# BottomSide.net
KiCad netlist of a schematic drawn in Altium Designer
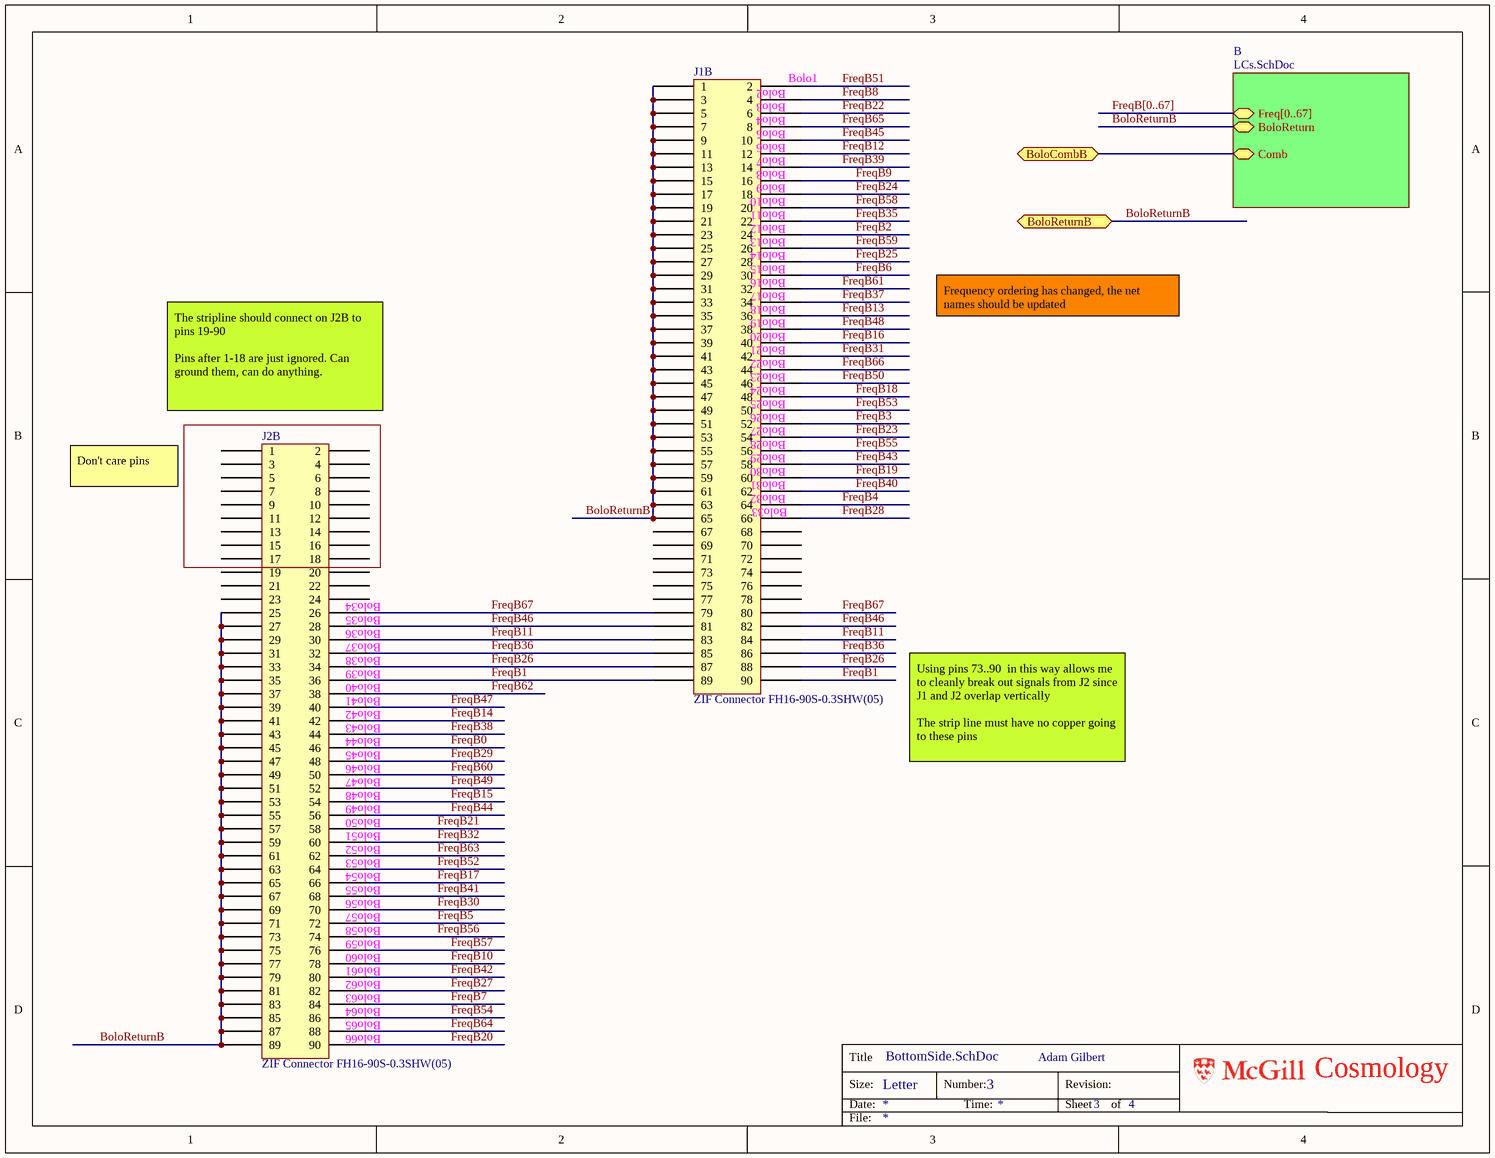
[diagram p0: BottomSide.SchDoc]

(export (version "E")
  (design (tool "Eeschema 10.0.6"))
  (components
    (comp (ref "J1B")
      (value "ZIF Connector FH16-90S-0.3SHW(05)")
      (footprint "LCBoard_ZIFCon")
      (libsource (lib "SPT3G_LCBoard") (part "LCboard_FH16-90S-0.3SHW(05)"))
    )
    (comp (ref "J2B")
      (value "ZIF Connector FH16-90S-0.3SHW(05)")
      (footprint "LCBoard_ZIFCon")
      (libsource (lib "SPT3G_LCBoard") (part "LCboard_FH16-90S-0.3SHW(05)"))
    )
  )
  (nets
    (net (code "4") (name "/BoloReturnB") (class "Default")
      (node (ref "J1B") (pin "1") (pinfunction "1_1") (pintype "passive"))
      (node (ref "J1B") (pin "11") (pinfunction "11_11") (pintype "passive"))
      (node (ref "J1B") (pin "13") (pinfunction "13_13") (pintype "passive"))
      (node (ref "J1B") (pin "15") (pinfunction "15_15") (pintype "passive"))
      (node (ref "J1B") (pin "17") (pinfunction "17_17") (pintype "passive"))
      (node (ref "J1B") (pin "19") (pinfunction "19_19") (pintype "passive"))
      (node (ref "J1B") (pin "21") (pinfunction "21_21") (pintype "passive"))
      (node (ref "J1B") (pin "23") (pinfunction "23_23") (pintype "passive"))
      (node (ref "J1B") (pin "25") (pinfunction "25_25") (pintype "passive"))
      (node (ref "J1B") (pin "27") (pinfunction "27_27") (pintype "passive"))
      (node (ref "J1B") (pin "29") (pinfunction "29_29") (pintype "passive"))
      (node (ref "J1B") (pin "3") (pinfunction "3_3") (pintype "passive"))
      (node (ref "J1B") (pin "31") (pinfunction "31_31") (pintype "passive"))
      (node (ref "J1B") (pin "33") (pinfunction "33_33") (pintype "passive"))
      (node (ref "J1B") (pin "35") (pinfunction "35_35") (pintype "passive"))
      (node (ref "J1B") (pin "37") (pinfunction "37_37") (pintype "passive"))
      (node (ref "J1B") (pin "39") (pinfunction "39_39") (pintype "passive"))
      (node (ref "J1B") (pin "41") (pinfunction "41_41") (pintype "passive"))
      (node (ref "J1B") (pin "43") (pinfunction "43_43") (pintype "passive"))
      (node (ref "J1B") (pin "45") (pinfunction "45_45") (pintype "passive"))
      (node (ref "J1B") (pin "47") (pinfunction "47_47") (pintype "passive"))
      (node (ref "J1B") (pin "49") (pinfunction "49_49") (pintype "passive"))
      (node (ref "J1B") (pin "5") (pinfunction "5_5") (pintype "passive"))
      (node (ref "J1B") (pin "51") (pinfunction "51_51") (pintype "passive"))
      (node (ref "J1B") (pin "53") (pinfunction "53_53") (pintype "passive"))
      (node (ref "J1B") (pin "55") (pinfunction "55_55") (pintype "passive"))
      (node (ref "J1B") (pin "57") (pinfunction "57_57") (pintype "passive"))
      (node (ref "J1B") (pin "59") (pinfunction "59_59") (pintype "passive"))
      (node (ref "J1B") (pin "61") (pinfunction "61_61") (pintype "passive"))
      (node (ref "J1B") (pin "63") (pinfunction "63_63") (pintype "passive"))
      (node (ref "J1B") (pin "65") (pinfunction "65_65") (pintype "passive"))
      (node (ref "J1B") (pin "7") (pinfunction "7_7") (pintype "passive"))
      (node (ref "J1B") (pin "9") (pinfunction "9_9") (pintype "passive"))
      (node (ref "J2B") (pin "25") (pinfunction "25_25") (pintype "passive"))
      (node (ref "J2B") (pin "27") (pinfunction "27_27") (pintype "passive"))
      (node (ref "J2B") (pin "29") (pinfunction "29_29") (pintype "passive"))
      (node (ref "J2B") (pin "31") (pinfunction "31_31") (pintype "passive"))
      (node (ref "J2B") (pin "33") (pinfunction "33_33") (pintype "passive"))
      (node (ref "J2B") (pin "35") (pinfunction "35_35") (pintype "passive"))
      (node (ref "J2B") (pin "37") (pinfunction "37_37") (pintype "passive"))
      (node (ref "J2B") (pin "39") (pinfunction "39_39") (pintype "passive"))
      (node (ref "J2B") (pin "41") (pinfunction "41_41") (pintype "passive"))
      (node (ref "J2B") (pin "43") (pinfunction "43_43") (pintype "passive"))
      (node (ref "J2B") (pin "45") (pinfunction "45_45") (pintype "passive"))
      (node (ref "J2B") (pin "47") (pinfunction "47_47") (pintype "passive"))
      (node (ref "J2B") (pin "49") (pinfunction "49_49") (pintype "passive"))
      (node (ref "J2B") (pin "51") (pinfunction "51_51") (pintype "passive"))
      (node (ref "J2B") (pin "53") (pinfunction "53_53") (pintype "passive"))
      (node (ref "J2B") (pin "55") (pinfunction "55_55") (pintype "passive"))
      (node (ref "J2B") (pin "57") (pinfunction "57_57") (pintype "passive"))
      (node (ref "J2B") (pin "59") (pinfunction "59_59") (pintype "passive"))
      (node (ref "J2B") (pin "61") (pinfunction "61_61") (pintype "passive"))
      (node (ref "J2B") (pin "63") (pinfunction "63_63") (pintype "passive"))
      (node (ref "J2B") (pin "65") (pinfunction "65_65") (pintype "passive"))
      (node (ref "J2B") (pin "67") (pinfunction "67_67") (pintype "passive"))
      (node (ref "J2B") (pin "69") (pinfunction "69_69") (pintype "passive"))
      (node (ref "J2B") (pin "71") (pinfunction "71_71") (pintype "passive"))
      (node (ref "J2B") (pin "73") (pinfunction "73_73") (pintype "passive"))
      (node (ref "J2B") (pin "75") (pinfunction "75_75") (pintype "passive"))
      (node (ref "J2B") (pin "77") (pinfunction "77_77") (pintype "passive"))
      (node (ref "J2B") (pin "79") (pinfunction "79_79") (pintype "passive"))
      (node (ref "J2B") (pin "81") (pinfunction "81_81") (pintype "passive"))
      (node (ref "J2B") (pin "83") (pinfunction "83_83") (pintype "passive"))
      (node (ref "J2B") (pin "85") (pinfunction "85_85") (pintype "passive"))
      (node (ref "J2B") (pin "87") (pinfunction "87_87") (pintype "passive"))
      (node (ref "J2B") (pin "89") (pinfunction "89_89") (pintype "passive"))
    )
    (net (code "5") (name "/FreqB0") (class "Default")
      (node (ref "J2B") (pin "46") (pinfunction "46_46") (pintype "passive"))
    )
    (net (code "6") (name "/FreqB1") (class "Default")
      (node (ref "J1B") (pin "89") (pinfunction "89_89") (pintype "passive"))
      (node (ref "J1B") (pin "90") (pinfunction "90_90") (pintype "passive"))
      (node (ref "J2B") (pin "36") (pinfunction "36_36") (pintype "passive"))
    )
    (net (code "7") (name "/FreqB2") (class "Default")
      (node (ref "J1B") (pin "24") (pinfunction "24_24") (pintype "passive"))
    )
    (net (code "8") (name "/FreqB3") (class "Default")
      (node (ref "J1B") (pin "52") (pinfunction "52_52") (pintype "passive"))
    )
    (net (code "9") (name "/FreqB4") (class "Default")
      (node (ref "J1B") (pin "64") (pinfunction "64_64") (pintype "passive"))
    )
    (net (code "10") (name "/FreqB5") (class "Default")
      (node (ref "J2B") (pin "72") (pinfunction "72_72") (pintype "passive"))
    )
    (net (code "11") (name "/FreqB6") (class "Default")
      (node (ref "J1B") (pin "30") (pinfunction "30_30") (pintype "passive"))
    )
    (net (code "12") (name "/FreqB7") (class "Default")
      (node (ref "J2B") (pin "84") (pinfunction "84_84") (pintype "passive"))
    )
    (net (code "13") (name "/FreqB8") (class "Default")
      (node (ref "J1B") (pin "4") (pinfunction "4_4") (pintype "passive"))
    )
    (net (code "14") (name "/FreqB9") (class "Default")
      (node (ref "J1B") (pin "16") (pinfunction "16_16") (pintype "passive"))
    )
    (net (code "15") (name "/FreqB10") (class "Default")
      (node (ref "J2B") (pin "78") (pinfunction "78_78") (pintype "passive"))
    )
    (net (code "16") (name "/FreqB11") (class "Default")
      (node (ref "J1B") (pin "83") (pinfunction "83_83") (pintype "passive"))
      (node (ref "J1B") (pin "84") (pinfunction "84_84") (pintype "passive"))
      (node (ref "J2B") (pin "30") (pinfunction "30_30") (pintype "passive"))
    )
    (net (code "17") (name "/FreqB12") (class "Default")
      (node (ref "J1B") (pin "12") (pinfunction "12_12") (pintype "passive"))
    )
    (net (code "18") (name "/FreqB13") (class "Default")
      (node (ref "J1B") (pin "36") (pinfunction "36_36") (pintype "passive"))
    )
    (net (code "19") (name "/FreqB14") (class "Default")
      (node (ref "J2B") (pin "42") (pinfunction "42_42") (pintype "passive"))
    )
    (net (code "20") (name "/FreqB15") (class "Default")
      (node (ref "J2B") (pin "54") (pinfunction "54_54") (pintype "passive"))
    )
    (net (code "21") (name "/FreqB16") (class "Default")
      (node (ref "J1B") (pin "40") (pinfunction "40_40") (pintype "passive"))
    )
    (net (code "22") (name "/FreqB17") (class "Default")
      (node (ref "J2B") (pin "66") (pinfunction "66_66") (pintype "passive"))
    )
    (net (code "23") (name "/FreqB18") (class "Default")
      (node (ref "J1B") (pin "48") (pinfunction "48_48") (pintype "passive"))
    )
    (net (code "24") (name "/FreqB19") (class "Default")
      (node (ref "J1B") (pin "60") (pinfunction "60_60") (pintype "passive"))
    )
    (net (code "25") (name "/FreqB20") (class "Default")
      (node (ref "J2B") (pin "90") (pinfunction "90_90") (pintype "passive"))
    )
    (net (code "26") (name "/FreqB21") (class "Default")
      (node (ref "J2B") (pin "58") (pinfunction "58_58") (pintype "passive"))
    )
    (net (code "27") (name "/FreqB22") (class "Default")
      (node (ref "J1B") (pin "6") (pinfunction "6_6") (pintype "passive"))
    )
    (net (code "28") (name "/FreqB23") (class "Default")
      (node (ref "J1B") (pin "54") (pinfunction "54_54") (pintype "passive"))
    )
    (net (code "29") (name "/FreqB24") (class "Default")
      (node (ref "J1B") (pin "18") (pinfunction "18_18") (pintype "passive"))
    )
    (net (code "30") (name "/FreqB25") (class "Default")
      (node (ref "J1B") (pin "28") (pinfunction "28_28") (pintype "passive"))
    )
    (net (code "31") (name "/FreqB26") (class "Default")
      (node (ref "J1B") (pin "87") (pinfunction "87_87") (pintype "passive"))
      (node (ref "J1B") (pin "88") (pinfunction "88_88") (pintype "passive"))
      (node (ref "J2B") (pin "34") (pinfunction "34_34") (pintype "passive"))
    )
    (net (code "32") (name "/FreqB27") (class "Default")
      (node (ref "J2B") (pin "82") (pinfunction "82_82") (pintype "passive"))
    )
    (net (code "33") (name "/FreqB28") (class "Default")
      (node (ref "J1B") (pin "66") (pinfunction "66_66") (pintype "passive"))
    )
    (net (code "34") (name "/FreqB29") (class "Default")
      (node (ref "J2B") (pin "48") (pinfunction "48_48") (pintype "passive"))
    )
    (net (code "35") (name "/FreqB30") (class "Default")
      (node (ref "J2B") (pin "70") (pinfunction "70_70") (pintype "passive"))
    )
    (net (code "36") (name "/FreqB31") (class "Default")
      (node (ref "J1B") (pin "42") (pinfunction "42_42") (pintype "passive"))
    )
    (net (code "37") (name "/FreqB32") (class "Default")
      (node (ref "J2B") (pin "60") (pinfunction "60_60") (pintype "passive"))
    )
    (net (code "38") (name "/FreqB35") (class "Default")
      (node (ref "J1B") (pin "22") (pinfunction "22_22") (pintype "passive"))
    )
    (net (code "39") (name "/FreqB36") (class "Default")
      (node (ref "J1B") (pin "85") (pinfunction "85_85") (pintype "passive"))
      (node (ref "J1B") (pin "86") (pinfunction "86_86") (pintype "passive"))
      (node (ref "J2B") (pin "32") (pinfunction "32_32") (pintype "passive"))
    )
    (net (code "40") (name "/FreqB37") (class "Default")
      (node (ref "J1B") (pin "34") (pinfunction "34_34") (pintype "passive"))
    )
    (net (code "41") (name "/FreqB38") (class "Default")
      (node (ref "J2B") (pin "44") (pinfunction "44_44") (pintype "passive"))
    )
    (net (code "42") (name "/FreqB39") (class "Default")
      (node (ref "J1B") (pin "14") (pinfunction "14_14") (pintype "passive"))
    )
    (net (code "43") (name "/FreqB40") (class "Default")
      (node (ref "J1B") (pin "62") (pinfunction "62_62") (pintype "passive"))
    )
    (net (code "44") (name "/FreqB41") (class "Default")
      (node (ref "J2B") (pin "68") (pinfunction "68_68") (pintype "passive"))
    )
    (net (code "45") (name "/FreqB42") (class "Default")
      (node (ref "J2B") (pin "80") (pinfunction "80_80") (pintype "passive"))
    )
    (net (code "46") (name "/FreqB43") (class "Default")
      (node (ref "J1B") (pin "58") (pinfunction "58_58") (pintype "passive"))
    )
    (net (code "47") (name "/FreqB44") (class "Default")
      (node (ref "J2B") (pin "56") (pinfunction "56_56") (pintype "passive"))
    )
    (net (code "48") (name "/FreqB45") (class "Default")
      (node (ref "J1B") (pin "10") (pinfunction "10_10") (pintype "passive"))
    )
    (net (code "49") (name "/FreqB46") (class "Default")
      (node (ref "J1B") (pin "81") (pinfunction "81_81") (pintype "passive"))
      (node (ref "J1B") (pin "82") (pinfunction "82_82") (pintype "passive"))
      (node (ref "J2B") (pin "28") (pinfunction "28_28") (pintype "passive"))
    )
    (net (code "50") (name "/FreqB47") (class "Default")
      (node (ref "J2B") (pin "40") (pinfunction "40_40") (pintype "passive"))
    )
    (net (code "51") (name "/FreqB48") (class "Default")
      (node (ref "J1B") (pin "38") (pinfunction "38_38") (pintype "passive"))
    )
    (net (code "52") (name "/FreqB49") (class "Default")
      (node (ref "J2B") (pin "52") (pinfunction "52_52") (pintype "passive"))
    )
    (net (code "53") (name "/FreqB50") (class "Default")
      (node (ref "J1B") (pin "46") (pinfunction "46_46") (pintype "passive"))
    )
    (net (code "54") (name "/FreqB51") (class "Default")
      (node (ref "J1B") (pin "2") (pinfunction "2_2") (pintype "passive"))
    )
    (net (code "55") (name "/FreqB52") (class "Default")
      (node (ref "J2B") (pin "64") (pinfunction "64_64") (pintype "passive"))
    )
    (net (code "56") (name "/FreqB53") (class "Default")
      (node (ref "J1B") (pin "50") (pinfunction "50_50") (pintype "passive"))
    )
    (net (code "57") (name "/FreqB54") (class "Default")
      (node (ref "J2B") (pin "86") (pinfunction "86_86") (pintype "passive"))
    )
    (net (code "58") (name "/FreqB55") (class "Default")
      (node (ref "J1B") (pin "56") (pinfunction "56_56") (pintype "passive"))
    )
    (net (code "59") (name "/FreqB56") (class "Default")
      (node (ref "J2B") (pin "74") (pinfunction "74_74") (pintype "passive"))
    )
    (net (code "60") (name "/FreqB57") (class "Default")
      (node (ref "J2B") (pin "76") (pinfunction "76_76") (pintype "passive"))
    )
    (net (code "61") (name "/FreqB58") (class "Default")
      (node (ref "J1B") (pin "20") (pinfunction "20_20") (pintype "passive"))
    )
    (net (code "62") (name "/FreqB59") (class "Default")
      (node (ref "J1B") (pin "26") (pinfunction "26_26") (pintype "passive"))
    )
    (net (code "63") (name "/FreqB60") (class "Default")
      (node (ref "J2B") (pin "50") (pinfunction "50_50") (pintype "passive"))
    )
    (net (code "64") (name "/FreqB61") (class "Default")
      (node (ref "J1B") (pin "32") (pinfunction "32_32") (pintype "passive"))
    )
    (net (code "65") (name "/FreqB62") (class "Default")
      (node (ref "J2B") (pin "38") (pinfunction "38_38") (pintype "passive"))
    )
    (net (code "66") (name "/FreqB63") (class "Default")
      (node (ref "J2B") (pin "62") (pinfunction "62_62") (pintype "passive"))
    )
    (net (code "67") (name "/FreqB64") (class "Default")
      (node (ref "J2B") (pin "88") (pinfunction "88_88") (pintype "passive"))
    )
    (net (code "68") (name "/FreqB65") (class "Default")
      (node (ref "J1B") (pin "8") (pinfunction "8_8") (pintype "passive"))
    )
    (net (code "69") (name "/FreqB66") (class "Default")
      (node (ref "J1B") (pin "44") (pinfunction "44_44") (pintype "passive"))
    )
    (net (code "70") (name "/FreqB67") (class "Default")
      (node (ref "J1B") (pin "79") (pinfunction "79_79") (pintype "passive"))
      (node (ref "J1B") (pin "80") (pinfunction "80_80") (pintype "passive"))
      (node (ref "J2B") (pin "26") (pinfunction "26_26") (pintype "passive"))
    )
    (net (code "72") (name "unconnected-(J1B-Pad67)") (class "Default")
      (node (ref "J1B") (pin "67") (pinfunction "67_67") (pintype "passive"))
    )
    (net (code "73") (name "unconnected-(J1B-Pad68)") (class "Default")
      (node (ref "J1B") (pin "68") (pinfunction "68_68") (pintype "passive"))
    )
    (net (code "74") (name "unconnected-(J1B-Pad69)") (class "Default")
      (node (ref "J1B") (pin "69") (pinfunction "69_69") (pintype "passive"))
    )
    (net (code "75") (name "unconnected-(J1B-Pad70)") (class "Default")
      (node (ref "J1B") (pin "70") (pinfunction "70_70") (pintype "passive"))
    )
    (net (code "76") (name "unconnected-(J1B-Pad71)") (class "Default")
      (node (ref "J1B") (pin "71") (pinfunction "71_71") (pintype "passive"))
    )
    (net (code "77") (name "unconnected-(J1B-Pad72)") (class "Default")
      (node (ref "J1B") (pin "72") (pinfunction "72_72") (pintype "passive"))
    )
    (net (code "78") (name "unconnected-(J1B-Pad73)") (class "Default")
      (node (ref "J1B") (pin "73") (pinfunction "73_73") (pintype "passive"))
    )
    (net (code "79") (name "unconnected-(J1B-Pad74)") (class "Default")
      (node (ref "J1B") (pin "74") (pinfunction "74_74") (pintype "passive"))
    )
    (net (code "80") (name "unconnected-(J1B-Pad75)") (class "Default")
      (node (ref "J1B") (pin "75") (pinfunction "75_75") (pintype "passive"))
    )
    (net (code "81") (name "unconnected-(J1B-Pad76)") (class "Default")
      (node (ref "J1B") (pin "76") (pinfunction "76_76") (pintype "passive"))
    )
    (net (code "82") (name "unconnected-(J1B-Pad77)") (class "Default")
      (node (ref "J1B") (pin "77") (pinfunction "77_77") (pintype "passive"))
    )
    (net (code "83") (name "unconnected-(J1B-Pad78)") (class "Default")
      (node (ref "J1B") (pin "78") (pinfunction "78_78") (pintype "passive"))
    )
    (net (code "84") (name "unconnected-(J2B-Pad1)") (class "Default")
      (node (ref "J2B") (pin "1") (pinfunction "1_1") (pintype "passive"))
    )
    (net (code "85") (name "unconnected-(J2B-Pad2)") (class "Default")
      (node (ref "J2B") (pin "2") (pinfunction "2_2") (pintype "passive"))
    )
    (net (code "86") (name "unconnected-(J2B-Pad3)") (class "Default")
      (node (ref "J2B") (pin "3") (pinfunction "3_3") (pintype "passive"))
    )
    (net (code "87") (name "unconnected-(J2B-Pad4)") (class "Default")
      (node (ref "J2B") (pin "4") (pinfunction "4_4") (pintype "passive"))
    )
    (net (code "88") (name "unconnected-(J2B-Pad5)") (class "Default")
      (node (ref "J2B") (pin "5") (pinfunction "5_5") (pintype "passive"))
    )
    (net (code "89") (name "unconnected-(J2B-Pad6)") (class "Default")
      (node (ref "J2B") (pin "6") (pinfunction "6_6") (pintype "passive"))
    )
    (net (code "90") (name "unconnected-(J2B-Pad7)") (class "Default")
      (node (ref "J2B") (pin "7") (pinfunction "7_7") (pintype "passive"))
    )
    (net (code "91") (name "unconnected-(J2B-Pad8)") (class "Default")
      (node (ref "J2B") (pin "8") (pinfunction "8_8") (pintype "passive"))
    )
    (net (code "92") (name "unconnected-(J2B-Pad9)") (class "Default")
      (node (ref "J2B") (pin "9") (pinfunction "9_9") (pintype "passive"))
    )
    (net (code "93") (name "unconnected-(J2B-Pad10)") (class "Default")
      (node (ref "J2B") (pin "10") (pinfunction "10_10") (pintype "passive"))
    )
    (net (code "94") (name "unconnected-(J2B-Pad11)") (class "Default")
      (node (ref "J2B") (pin "11") (pinfunction "11_11") (pintype "passive"))
    )
    (net (code "95") (name "unconnected-(J2B-Pad12)") (class "Default")
      (node (ref "J2B") (pin "12") (pinfunction "12_12") (pintype "passive"))
    )
    (net (code "96") (name "unconnected-(J2B-Pad13)") (class "Default")
      (node (ref "J2B") (pin "13") (pinfunction "13_13") (pintype "passive"))
    )
    (net (code "97") (name "unconnected-(J2B-Pad14)") (class "Default")
      (node (ref "J2B") (pin "14") (pinfunction "14_14") (pintype "passive"))
    )
    (net (code "98") (name "unconnected-(J2B-Pad15)") (class "Default")
      (node (ref "J2B") (pin "15") (pinfunction "15_15") (pintype "passive"))
    )
    (net (code "99") (name "unconnected-(J2B-Pad16)") (class "Default")
      (node (ref "J2B") (pin "16") (pinfunction "16_16") (pintype "passive"))
    )
    (net (code "100") (name "unconnected-(J2B-Pad17)") (class "Default")
      (node (ref "J2B") (pin "17") (pinfunction "17_17") (pintype "passive"))
    )
    (net (code "101") (name "unconnected-(J2B-Pad18)") (class "Default")
      (node (ref "J2B") (pin "18") (pinfunction "18_18") (pintype "passive"))
    )
    (net (code "102") (name "unconnected-(J2B-Pad19)") (class "Default")
      (node (ref "J2B") (pin "19") (pinfunction "19_19") (pintype "passive"))
    )
    (net (code "103") (name "unconnected-(J2B-Pad20)") (class "Default")
      (node (ref "J2B") (pin "20") (pinfunction "20_20") (pintype "passive"))
    )
    (net (code "104") (name "unconnected-(J2B-Pad21)") (class "Default")
      (node (ref "J2B") (pin "21") (pinfunction "21_21") (pintype "passive"))
    )
    (net (code "105") (name "unconnected-(J2B-Pad22)") (class "Default")
      (node (ref "J2B") (pin "22") (pinfunction "22_22") (pintype "passive"))
    )
    (net (code "106") (name "unconnected-(J2B-Pad23)") (class "Default")
      (node (ref "J2B") (pin "23") (pinfunction "23_23") (pintype "passive"))
    )
    (net (code "107") (name "unconnected-(J2B-Pad24)") (class "Default")
      (node (ref "J2B") (pin "24") (pinfunction "24_24") (pintype "passive"))
    )
  )
)
